# door_unlocker.net
KiCad netlist of a schematic drawn in EAGLE
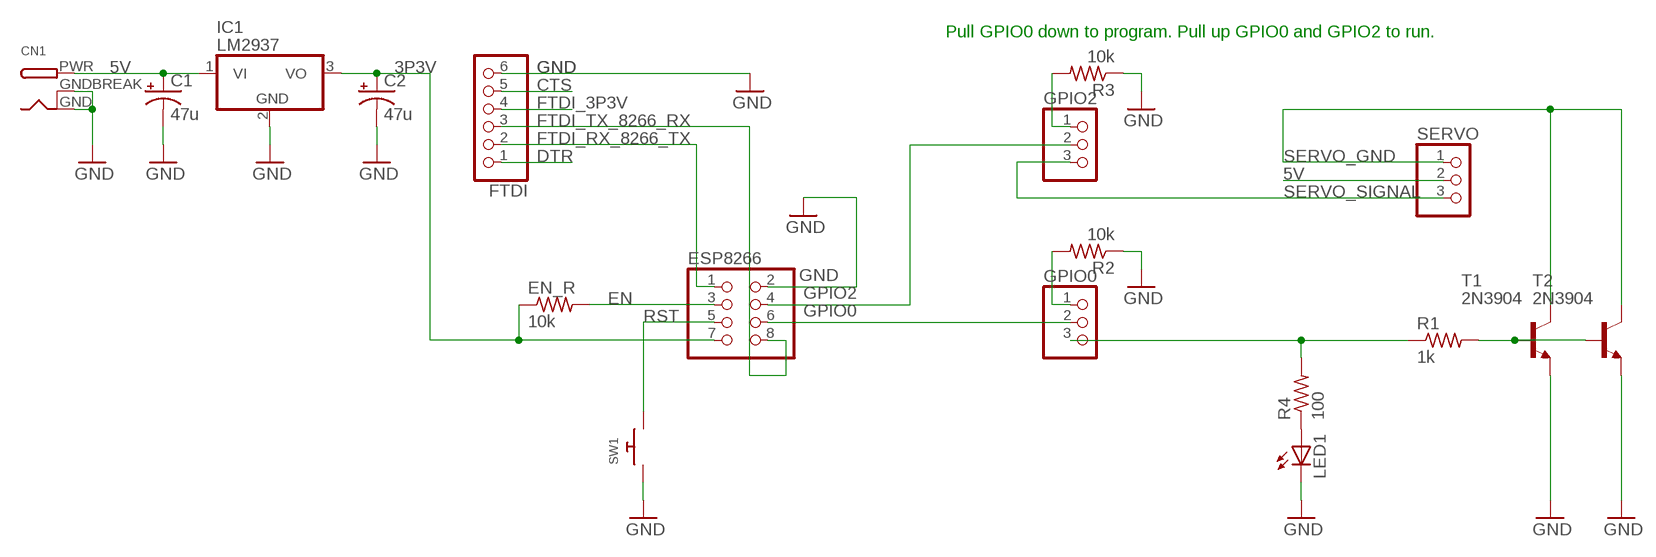
[diagram p0: schematic, sheet 1]

(export (version "E")
  (design (tool "Eeschema 10.0.6"))
  (components
    (comp (ref "C1")
      (value "47u")
      (footprint "eagle-import:E2,5-6E")
      (libsource (lib "eagle-import") (part "CPOL-USE2,5-6E"))
    )
    (comp (ref "C2")
      (value "47u")
      (footprint "eagle-import:E2,5-6E")
      (libsource (lib "eagle-import") (part "CPOL-USE2,5-6E"))
    )
    (comp (ref "CN1")
      (value "DCBARRELPTH")
      (footprint "eagle-import:DCJACK_2MM_PTH")
      (libsource (lib "eagle-import") (part "DCBARRELPTH"))
    )
    (comp (ref "EN_R")
      (value "10k")
      (footprint "eagle-import:0207_10")
      (libsource (lib "eagle-import") (part "R-US_0207/10"))
    )
    (comp (ref "ESP8266")
      (value "PINHD-2X4")
      (footprint "eagle-import:2X04")
      (libsource (lib "eagle-import") (part "PINHD-2X4"))
    )
    (comp (ref "FTDI")
      (value "PINHD-1X6")
      (footprint "eagle-import:1X06")
      (libsource (lib "eagle-import") (part "PINHD-1X6"))
    )
    (comp (ref "GPIO0")
      (value "PINHD-1X3")
      (footprint "eagle-import:1X03")
      (libsource (lib "eagle-import") (part "PINHD-1X3"))
    )
    (comp (ref "GPIO2")
      (value "PINHD-1X3")
      (footprint "eagle-import:1X03")
      (libsource (lib "eagle-import") (part "PINHD-1X3"))
    )
    (comp (ref "IC1")
      (value "LM2937")
      (footprint "eagle-import:TO263-3")
      (libsource (lib "eagle-import") (part "LM2937"))
    )
    (comp (ref "LED1")
      (value "LED5MM")
      (footprint "eagle-import:LED5MM")
      (libsource (lib "eagle-import") (part "LED5MM"))
    )
    (comp (ref "R1")
      (value "1k")
      (footprint "eagle-import:0207_10")
      (libsource (lib "eagle-import") (part "R-US_0207/10"))
    )
    (comp (ref "R2")
      (value "10k")
      (footprint "eagle-import:0207_10")
      (libsource (lib "eagle-import") (part "R-US_0207/10"))
    )
    (comp (ref "R3")
      (value "10k")
      (footprint "eagle-import:0207_10")
      (libsource (lib "eagle-import") (part "R-US_0207/10"))
    )
    (comp (ref "R4")
      (value "100")
      (footprint "eagle-import:0207_10")
      (libsource (lib "eagle-import") (part "R-US_0207/10"))
    )
    (comp (ref "SERVO")
      (value "PINHD-1X3")
      (footprint "eagle-import:1X03")
      (libsource (lib "eagle-import") (part "PINHD-1X3"))
    )
    (comp (ref "SW1")
      (value "SWITCH_PUSHBUTTONEVQ-PE")
      (footprint "eagle-import:TACT_PANA-EVQ")
      (libsource (lib "eagle-import") (part "SWITCH_PUSHBUTTONEVQ-PE"))
    )
    (comp (ref "T1")
      (value "2N3904")
      (footprint "eagle-import:TO92")
      (libsource (lib "eagle-import") (part "2N3904"))
    )
    (comp (ref "T2")
      (value "2N3904")
      (footprint "eagle-import:TO92")
      (libsource (lib "eagle-import") (part "2N3904"))
    )
  )
  (nets
    (net (code "1") (name "/3P3V") (class "Default")
      (node (ref "C2") (pin "+") (pinfunction "+_+") (pintype "passive"))
      (node (ref "EN_R") (pin "1") (pinfunction "1_1") (pintype "passive"))
      (node (ref "ESP8266") (pin "7") (pinfunction "7_7") (pintype "passive"))
      (node (ref "IC1") (pin "3") (pinfunction "VO_3") (pintype "passive"))
    )
    (net (code "2") (name "/5V") (class "Default")
      (node (ref "C1") (pin "+") (pinfunction "+_+") (pintype "passive"))
      (node (ref "CN1") (pin "PWR") (pinfunction "PWR_PWR") (pintype "power_in"))
      (node (ref "IC1") (pin "1") (pinfunction "VI_1") (pintype "input"))
      (node (ref "SERVO") (pin "2") (pinfunction "2_2") (pintype "passive"))
    )
    (net (code "3") (name "/CTS") (class "Default")
      (node (ref "FTDI") (pin "5") (pinfunction "5_5") (pintype "passive"))
    )
    (net (code "4") (name "/DTR") (class "Default")
      (node (ref "FTDI") (pin "1") (pinfunction "1_1") (pintype "passive"))
    )
    (net (code "5") (name "/EN") (class "Default")
      (node (ref "EN_R") (pin "2") (pinfunction "2_2") (pintype "passive"))
      (node (ref "ESP8266") (pin "3") (pinfunction "3_3") (pintype "passive"))
    )
    (net (code "6") (name "/FTDI_3P3V") (class "Default")
      (node (ref "FTDI") (pin "4") (pinfunction "4_4") (pintype "passive"))
    )
    (net (code "7") (name "/FTDI_RX_8266_TX") (class "Default")
      (node (ref "ESP8266") (pin "1") (pinfunction "1_1") (pintype "passive"))
      (node (ref "FTDI") (pin "2") (pinfunction "2_2") (pintype "passive"))
    )
    (net (code "8") (name "/FTDI_TX_8266_RX") (class "Default")
      (node (ref "ESP8266") (pin "8") (pinfunction "8_8") (pintype "passive"))
      (node (ref "FTDI") (pin "3") (pinfunction "3_3") (pintype "passive"))
    )
    (net (code "9") (name "/GPIO0") (class "Default")
      (node (ref "ESP8266") (pin "6") (pinfunction "6_6") (pintype "passive"))
      (node (ref "GPIO0") (pin "2") (pinfunction "2_2") (pintype "passive"))
    )
    (net (code "10") (name "/GPIO2") (class "Default")
      (node (ref "ESP8266") (pin "4") (pinfunction "4_4") (pintype "passive"))
      (node (ref "GPIO2") (pin "2") (pinfunction "2_2") (pintype "passive"))
    )
    (net (code "11") (name "/RST") (class "Default")
      (node (ref "ESP8266") (pin "5") (pinfunction "5_5") (pintype "passive"))
      (node (ref "SW1") (pin "P$2") (pinfunction "P$2_P$2") (pintype "passive"))
    )
    (net (code "12") (name "/SERVO_GND") (class "Default")
      (node (ref "SERVO") (pin "1") (pinfunction "1_1") (pintype "passive"))
      (node (ref "T1") (pin "1") (pinfunction "C_1") (pintype "passive"))
      (node (ref "T2") (pin "1") (pinfunction "C_1") (pintype "passive"))
    )
    (net (code "13") (name "/SERVO_SIGNAL") (class "Default")
      (node (ref "GPIO2") (pin "3") (pinfunction "3_3") (pintype "passive"))
      (node (ref "SERVO") (pin "3") (pinfunction "3_3") (pintype "passive"))
    )
    (net (code "14") (name "GND") (class "Default")
      (node (ref "C1") (pin "-") (pinfunction "-_-") (pintype "passive"))
      (node (ref "C2") (pin "-") (pinfunction "-_-") (pintype "passive"))
      (node (ref "CN1") (pin "GND") (pinfunction "GND_GND") (pintype "power_in"))
      (node (ref "CN1") (pin "GNDBREAK") (pinfunction "GNDBREAK_GNDBREAK") (pintype "power_in"))
      (node (ref "ESP8266") (pin "2") (pinfunction "2_2") (pintype "passive"))
      (node (ref "FTDI") (pin "6") (pinfunction "6_6") (pintype "passive"))
      (node (ref "IC1") (pin "2") (pinfunction "GND_2") (pintype "passive"))
      (node (ref "LED1") (pin "K") (pinfunction "C_K") (pintype "passive"))
      (node (ref "R2") (pin "1") (pinfunction "1_1") (pintype "passive"))
      (node (ref "R3") (pin "1") (pinfunction "1_1") (pintype "passive"))
      (node (ref "SW1") (pin "P$1") (pinfunction "P$1_P$1") (pintype "passive"))
      (node (ref "T1") (pin "3") (pinfunction "E_3") (pintype "passive"))
      (node (ref "T2") (pin "3") (pinfunction "E_3") (pintype "passive"))
    )
    (net (code "15") (name "Net-(GPIO0-Pad1)") (class "Default")
      (node (ref "GPIO0") (pin "1") (pinfunction "1_1") (pintype "passive"))
      (node (ref "R2") (pin "2") (pinfunction "2_2") (pintype "passive"))
    )
    (net (code "16") (name "Net-(GPIO0-Pad3)") (class "Default")
      (node (ref "GPIO0") (pin "3") (pinfunction "3_3") (pintype "passive"))
      (node (ref "R1") (pin "1") (pinfunction "1_1") (pintype "passive"))
      (node (ref "R4") (pin "2") (pinfunction "2_2") (pintype "passive"))
    )
    (net (code "17") (name "Net-(GPIO2-Pad1)") (class "Default")
      (node (ref "GPIO2") (pin "1") (pinfunction "1_1") (pintype "passive"))
      (node (ref "R3") (pin "2") (pinfunction "2_2") (pintype "passive"))
    )
    (net (code "18") (name "Net-(LED1-PadA)") (class "Default")
      (node (ref "LED1") (pin "A") (pinfunction "A_A") (pintype "passive"))
      (node (ref "R4") (pin "1") (pinfunction "1_1") (pintype "passive"))
    )
    (net (code "19") (name "Net-(T1-B)") (class "Default")
      (node (ref "R1") (pin "2") (pinfunction "2_2") (pintype "passive"))
      (node (ref "T1") (pin "2") (pinfunction "B_2") (pintype "passive"))
      (node (ref "T2") (pin "2") (pinfunction "B_2") (pintype "passive"))
    )
  )
)
